# Sheet1.net
KiCad netlist of a schematic drawn in Altium Designer
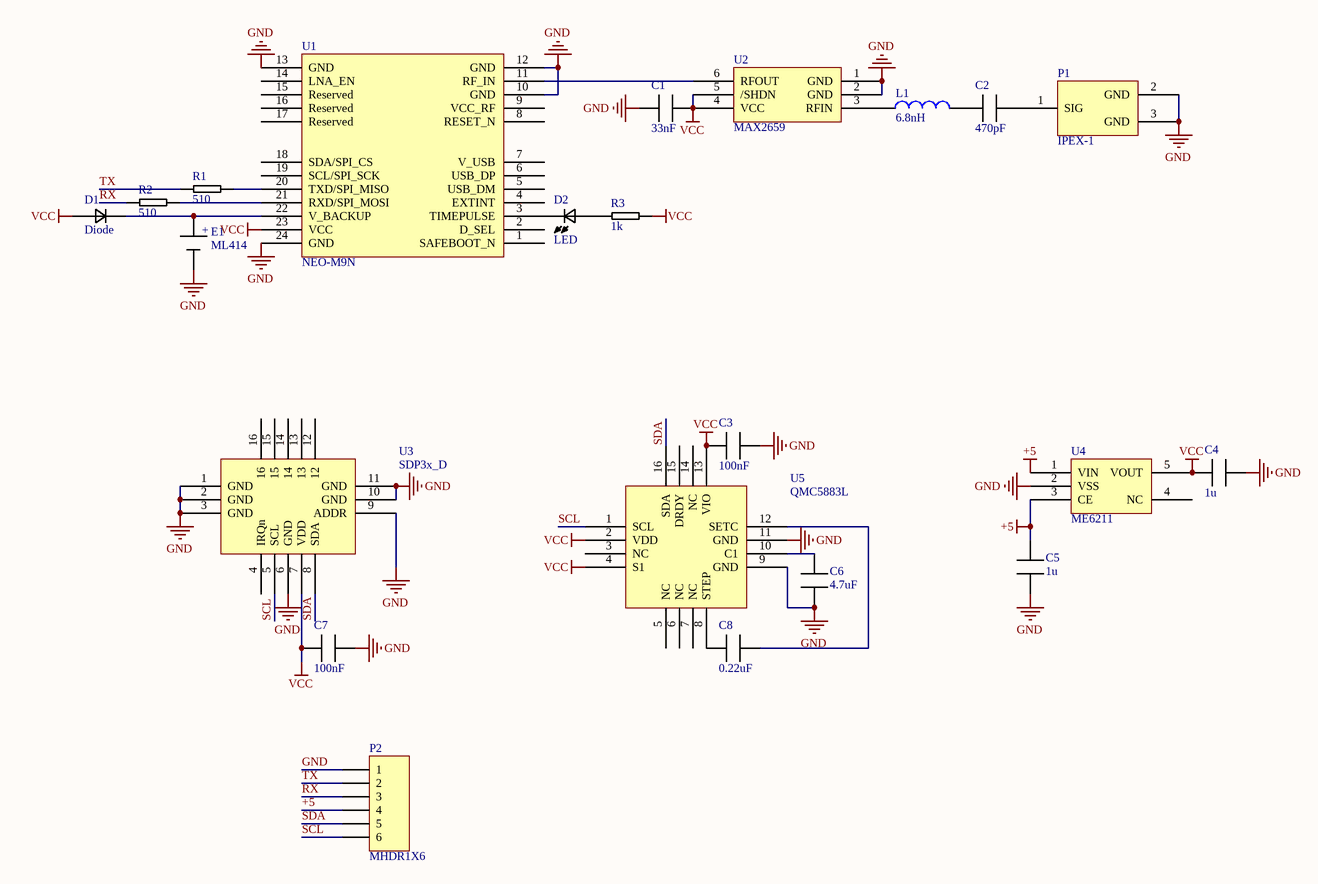
[diagram p0: Sheet1.SchDoc]

(export (version "E")
  (design (tool "Eeschema 10.0.6"))
  (components
    (comp (ref "C1") (value "33nF") (footprint "0603-Cap") (libsource (lib "LibCfrpg") (part "Cap")))
    (comp (ref "C2") (value "470pF") (footprint "0603-Cap") (libsource (lib "LibCfrpg") (part "Cap")))
    (comp (ref "C3") (value "100nF") (footprint "0603") (libsource (lib "LibCfrpg") (part "Cap")))
    (comp (ref "C4") (value "1u") (footprint "0603-Cap") (libsource (lib "LibCfrpg") (part "Cap")))
    (comp (ref "C5") (value "1u") (footprint "0603-Cap") (libsource (lib "LibCfrpg") (part "Cap")))
    (comp (ref "C6") (value "4.7uF") (footprint "0603") (libsource (lib "LibCfrpg") (part "Cap")))
    (comp (ref "C7") (value "100nF") (footprint "0603") (libsource (lib "LibCfrpg") (part "Cap")))
    (comp (ref "C8") (value "0.22uF") (footprint "0603") (libsource (lib "LibCfrpg") (part "Cap")))
    (comp (ref "D1") (value "Diode") (footprint "SOD-523") (libsource (lib "LibCfrpg") (part "Diode")))
    (comp (ref "D2") (value "LED") (footprint "0603-1") (libsource (lib "LibCfrpg") (part "LED")))
    (comp (ref "E1") (value "ML414") (footprint "ML-414") (libsource (lib "LibCfrpg") (part "BAT")))
    (comp (ref "L1")
      (value "6.8nH")
      (footprint "LibCfrpg:0603")
      (libsource (lib "LibCfrpg") (part "Inductor"))
    )
    (comp (ref "P1") (value "IPEX-1") (footprint "IPEX-1") (libsource (lib "LibCfrpg") (part "IPEX-1")))
    (comp (ref "P2")
      (value "MHDR1X6")
      (footprint "MHDR1X6")
      (description "Header, 6-Pin")
      (fields (field (name "PUBLISHER") "Altium Limited"))
      (libsource (lib "Miscellaneous Connectors") (part "MHDR1X6"))
    )
    (comp (ref "R1") (value "510") (footprint "0603") (libsource (lib "LibCfrpg") (part "Res")))
    (comp (ref "R2") (value "510") (footprint "0603") (libsource (lib "LibCfrpg") (part "Res")))
    (comp (ref "R3") (value "1k") (footprint "0603") (libsource (lib "LibCfrpg") (part "Res")))
    (comp (ref "U1") (value "NEO-M9N") (footprint "NEO-M9N") (libsource (lib "LibCfrpg") (part "NEO-M9N")))
    (comp (ref "U2") (value "MAX2659") (footprint "uDFN-6") (libsource (lib "LibCfrpg") (part "MAX2659")))
    (comp (ref "U3") (value "SDP3x_D") (footprint "SDP3x") (libsource (lib "LibCfrpg") (part "SDP3x_D")))
    (comp (ref "U4") (value "ME6211") (footprint "SC70-5") (libsource (lib "LibCfrpg") (part "ME6211")))
    (comp (ref "U5") (value "QMC5883L") (footprint "QMC5883") (libsource (lib "LibCfrpg") (part "QMC5883L")))
  )
  (nets
    (net (code "1") (name "+5") (class "Default")
      (node (ref "C5") (pin "2") (pintype "passive"))
      (node (ref "P2") (pin "4") (pinfunction "4_4") (pintype "passive"))
      (node (ref "U4") (pin "1") (pinfunction "VIN_1") (pintype "passive"))
      (node (ref "U4") (pin "3") (pinfunction "CE_3") (pintype "passive"))
    )
    (net (code "2") (name "/RX") (class "Default")
      (node (ref "P2") (pin "3") (pinfunction "3_3") (pintype "passive"))
      (node (ref "R2") (pin "1") (pintype "passive"))
    )
    (net (code "3") (name "/SCL") (class "Default")
      (node (ref "P2") (pin "6") (pinfunction "6_6") (pintype "passive"))
      (node (ref "U3") (pin "5") (pinfunction "SCL_5") (pintype "passive"))
      (node (ref "U5") (pin "1") (pinfunction "SCL_1") (pintype "passive"))
    )
    (net (code "4") (name "/SDA") (class "Default")
      (node (ref "P2") (pin "5") (pinfunction "5_5") (pintype "passive"))
      (node (ref "U3") (pin "8") (pinfunction "SDA_8") (pintype "passive"))
      (node (ref "U5") (pin "16") (pinfunction "SDA_16") (pintype "passive"))
    )
    (net (code "5") (name "/TX") (class "Default")
      (node (ref "P2") (pin "2") (pinfunction "2_2") (pintype "passive"))
      (node (ref "R1") (pin "1") (pintype "passive"))
    )
    (net (code "6") (name "GND") (class "Default")
      (node (ref "C1") (pin "1") (pintype "passive"))
      (node (ref "C3") (pin "2") (pintype "passive"))
      (node (ref "C4") (pin "2") (pintype "passive"))
      (node (ref "C5") (pin "1") (pintype "passive"))
      (node (ref "C6") (pin "1") (pintype "passive"))
      (node (ref "C7") (pin "2") (pintype "passive"))
      (node (ref "E1") (pin "2") (pintype "passive"))
      (node (ref "P1") (pin "2") (pinfunction "GND_2") (pintype "passive"))
      (node (ref "P1") (pin "3") (pinfunction "GND_3") (pintype "passive"))
      (node (ref "P2") (pin "1") (pinfunction "1_1") (pintype "passive"))
      (node (ref "U1") (pin "10") (pinfunction "GND_10") (pintype "passive"))
      (node (ref "U1") (pin "12") (pinfunction "GND_12") (pintype "passive"))
      (node (ref "U1") (pin "13") (pinfunction "GND_13") (pintype "passive"))
      (node (ref "U1") (pin "24") (pinfunction "GND_24") (pintype "passive"))
      (node (ref "U2") (pin "1") (pinfunction "GND_1") (pintype "passive"))
      (node (ref "U2") (pin "2") (pinfunction "GND_2") (pintype "passive"))
      (node (ref "U3") (pin "1") (pinfunction "GND_1") (pintype "passive"))
      (node (ref "U3") (pin "10") (pinfunction "GND_10") (pintype "passive"))
      (node (ref "U3") (pin "11") (pinfunction "GND_11") (pintype "passive"))
      (node (ref "U3") (pin "2") (pinfunction "GND_2") (pintype "passive"))
      (node (ref "U3") (pin "3") (pinfunction "GND_3") (pintype "passive"))
      (node (ref "U3") (pin "6") (pinfunction "GND_6") (pintype "passive"))
      (node (ref "U3") (pin "9") (pinfunction "ADDR_9") (pintype "passive"))
      (node (ref "U4") (pin "2") (pinfunction "VSS_2") (pintype "passive"))
      (node (ref "U5") (pin "11") (pinfunction "GND_11") (pintype "passive"))
      (node (ref "U5") (pin "9") (pinfunction "GND_9") (pintype "passive"))
    )
    (net (code "7") (name "Net-(C2-Pad1)") (class "Default")
      (node (ref "C2") (pin "1") (pintype "passive"))
      (node (ref "L1") (pin "2") (pinfunction "2_2") (pintype "passive"))
    )
    (net (code "8") (name "Net-(D2-Pad1)") (class "Default")
      (node (ref "D2") (pin "1") (pintype "passive"))
      (node (ref "R3") (pin "1") (pintype "passive"))
    )
    (net (code "9") (name "Net-(P1-SIG)") (class "Default")
      (node (ref "C2") (pin "2") (pintype "passive"))
      (node (ref "P1") (pin "1") (pinfunction "SIG_1") (pintype "passive"))
    )
    (net (code "10") (name "Net-(U1-RF_IN)") (class "Default")
      (node (ref "U1") (pin "11") (pinfunction "RF_IN_11") (pintype "passive"))
      (node (ref "U2") (pin "6") (pinfunction "RFOUT_6") (pintype "passive"))
    )
    (net (code "11") (name "Net-(U1-RXD{slash}SPI_MOSI)") (class "Default")
      (node (ref "R2") (pin "2") (pintype "passive"))
      (node (ref "U1") (pin "21") (pinfunction "RXD/SPI_MOSI_21") (pintype "passive"))
    )
    (net (code "12") (name "Net-(U1-TIMEPULSE)") (class "Default")
      (node (ref "D2") (pin "2") (pintype "passive"))
      (node (ref "U1") (pin "3") (pinfunction "TIMEPULSE_3") (pintype "passive"))
    )
    (net (code "13") (name "Net-(U1-TXD{slash}SPI_MISO)") (class "Default")
      (node (ref "R1") (pin "2") (pintype "passive"))
      (node (ref "U1") (pin "20") (pinfunction "TXD/SPI_MISO_20") (pintype "passive"))
    )
    (net (code "14") (name "Net-(U1-V_BACKUP)") (class "Default")
      (node (ref "D1") (pin "2") (pintype "passive"))
      (node (ref "E1") (pin "1") (pintype "passive"))
      (node (ref "U1") (pin "22") (pinfunction "V_BACKUP_22") (pintype "passive"))
    )
    (net (code "15") (name "Net-(U2-RFIN)") (class "Default")
      (node (ref "L1") (pin "1") (pinfunction "1_1") (pintype "passive"))
      (node (ref "U2") (pin "3") (pinfunction "RFIN_3") (pintype "passive"))
    )
    (net (code "16") (name "Net-(U5-C1)") (class "Default")
      (node (ref "C6") (pin "2") (pintype "passive"))
      (node (ref "U5") (pin "10") (pinfunction "C1_10") (pintype "passive"))
    )
    (net (code "17") (name "Net-(U5-SETC)") (class "Default")
      (node (ref "C8") (pin "2") (pintype "passive"))
      (node (ref "U5") (pin "12") (pinfunction "SETC_12") (pintype "passive"))
    )
    (net (code "18") (name "Net-(U5-STEP)") (class "Default")
      (node (ref "C8") (pin "1") (pintype "passive"))
      (node (ref "U5") (pin "8") (pinfunction "STEP_8") (pintype "passive"))
    )
    (net (code "19") (name "VCC") (class "Default")
      (node (ref "C1") (pin "2") (pintype "passive"))
      (node (ref "C3") (pin "1") (pintype "passive"))
      (node (ref "C4") (pin "1") (pintype "passive"))
      (node (ref "C7") (pin "1") (pintype "passive"))
      (node (ref "D1") (pin "1") (pintype "passive"))
      (node (ref "R3") (pin "2") (pintype "passive"))
      (node (ref "U1") (pin "23") (pinfunction "VCC_23") (pintype "passive"))
      (node (ref "U2") (pin "4") (pinfunction "VCC_4") (pintype "passive"))
      (node (ref "U2") (pin "5") (pinfunction "/SHDN_5") (pintype "passive"))
      (node (ref "U3") (pin "7") (pinfunction "VDD_7") (pintype "passive"))
      (node (ref "U4") (pin "5") (pinfunction "VOUT_5") (pintype "passive"))
      (node (ref "U5") (pin "13") (pinfunction "VIO_13") (pintype "passive"))
      (node (ref "U5") (pin "2") (pinfunction "VDD_2") (pintype "passive"))
      (node (ref "U5") (pin "4") (pinfunction "S1_4") (pintype "passive"))
    )
    (net (code "20") (name "unconnected-(U1-D_SEL-Pad2)") (class "Default")
      (node (ref "U1") (pin "2") (pinfunction "D_SEL_2") (pintype "passive"))
    )
    (net (code "21") (name "unconnected-(U1-EXTINT-Pad4)") (class "Default")
      (node (ref "U1") (pin "4") (pinfunction "EXTINT_4") (pintype "passive"))
    )
    (net (code "22") (name "unconnected-(U1-LNA_EN-Pad14)") (class "Default")
      (node (ref "U1") (pin "14") (pinfunction "LNA_EN_14") (pintype "passive"))
    )
    (net (code "23") (name "unconnected-(U1-RESET_N-Pad8)") (class "Default")
      (node (ref "U1") (pin "8") (pinfunction "RESET_N_8") (pintype "passive"))
    )
    (net (code "24") (name "unconnected-(U1-Reserved-Pad15)") (class "Default")
      (node (ref "U1") (pin "15") (pinfunction "Reserved_15") (pintype "passive"))
    )
    (net (code "25") (name "unconnected-(U1-Reserved-Pad16)") (class "Default")
      (node (ref "U1") (pin "16") (pinfunction "Reserved_16") (pintype "passive"))
    )
    (net (code "26") (name "unconnected-(U1-Reserved-Pad17)") (class "Default")
      (node (ref "U1") (pin "17") (pinfunction "Reserved_17") (pintype "passive"))
    )
    (net (code "27") (name "unconnected-(U1-SAFEBOOT_N-Pad1)") (class "Default")
      (node (ref "U1") (pin "1") (pinfunction "SAFEBOOT_N_1") (pintype "passive"))
    )
    (net (code "28") (name "unconnected-(U1-SCL{slash}SPI_SCK-Pad19)") (class "Default")
      (node (ref "U1") (pin "19") (pinfunction "SCL/SPI_SCK_19") (pintype "passive"))
    )
    (net (code "29") (name "unconnected-(U1-SDA{slash}SPI_CS-Pad18)") (class "Default")
      (node (ref "U1") (pin "18") (pinfunction "SDA/SPI_CS_18") (pintype "passive"))
    )
    (net (code "30") (name "unconnected-(U1-USB_DM-Pad5)") (class "Default")
      (node (ref "U1") (pin "5") (pinfunction "USB_DM_5") (pintype "passive"))
    )
    (net (code "31") (name "unconnected-(U1-USB_DP-Pad6)") (class "Default")
      (node (ref "U1") (pin "6") (pinfunction "USB_DP_6") (pintype "passive"))
    )
    (net (code "32") (name "unconnected-(U1-VCC_RF-Pad9)") (class "Default")
      (node (ref "U1") (pin "9") (pinfunction "VCC_RF_9") (pintype "passive"))
    )
    (net (code "33") (name "unconnected-(U1-V_USB-Pad7)") (class "Default")
      (node (ref "U1") (pin "7") (pinfunction "V_USB_7") (pintype "passive"))
    )
    (net (code "34") (name "unconnected-(U3-IRQn-Pad4)") (class "Default")
      (node (ref "U3") (pin "4") (pinfunction "IRQn_4") (pintype "passive"))
    )
    (net (code "35") (name "unconnected-(U3-Pad12)") (class "Default")
      (node (ref "U3") (pin "12") (pinfunction "12_12") (pintype "passive"))
    )
    (net (code "36") (name "unconnected-(U3-Pad13)") (class "Default")
      (node (ref "U3") (pin "13") (pinfunction "13_13") (pintype "passive"))
    )
    (net (code "37") (name "unconnected-(U3-Pad14)") (class "Default")
      (node (ref "U3") (pin "14") (pinfunction "14_14") (pintype "passive"))
    )
    (net (code "38") (name "unconnected-(U3-Pad15)") (class "Default")
      (node (ref "U3") (pin "15") (pinfunction "15_15") (pintype "passive"))
    )
    (net (code "39") (name "unconnected-(U3-Pad16)") (class "Default")
      (node (ref "U3") (pin "16") (pinfunction "16_16") (pintype "passive"))
    )
    (net (code "40") (name "unconnected-(U4-NC-Pad4)") (class "Default")
      (node (ref "U4") (pin "4") (pinfunction "NC_4") (pintype "passive"))
    )
    (net (code "41") (name "unconnected-(U5-DRDY-Pad15)") (class "Default")
      (node (ref "U5") (pin "15") (pinfunction "DRDY_15") (pintype "passive"))
    )
    (net (code "42") (name "unconnected-(U5-NC-Pad3)") (class "Default")
      (node (ref "U5") (pin "3") (pinfunction "NC_3") (pintype "passive"))
    )
    (net (code "43") (name "unconnected-(U5-NC-Pad5)") (class "Default")
      (node (ref "U5") (pin "5") (pinfunction "NC_5") (pintype "passive"))
    )
    (net (code "44") (name "unconnected-(U5-NC-Pad6)") (class "Default")
      (node (ref "U5") (pin "6") (pinfunction "NC_6") (pintype "passive"))
    )
    (net (code "45") (name "unconnected-(U5-NC-Pad7)") (class "Default")
      (node (ref "U5") (pin "7") (pinfunction "NC_7") (pintype "passive"))
    )
    (net (code "46") (name "unconnected-(U5-NC-Pad14)") (class "Default")
      (node (ref "U5") (pin "14") (pinfunction "NC_14") (pintype "passive"))
    )
  )
)
